# sx1509-breakout_mount_remap5.net
KiCad netlist of a schematic drawn in EAGLE
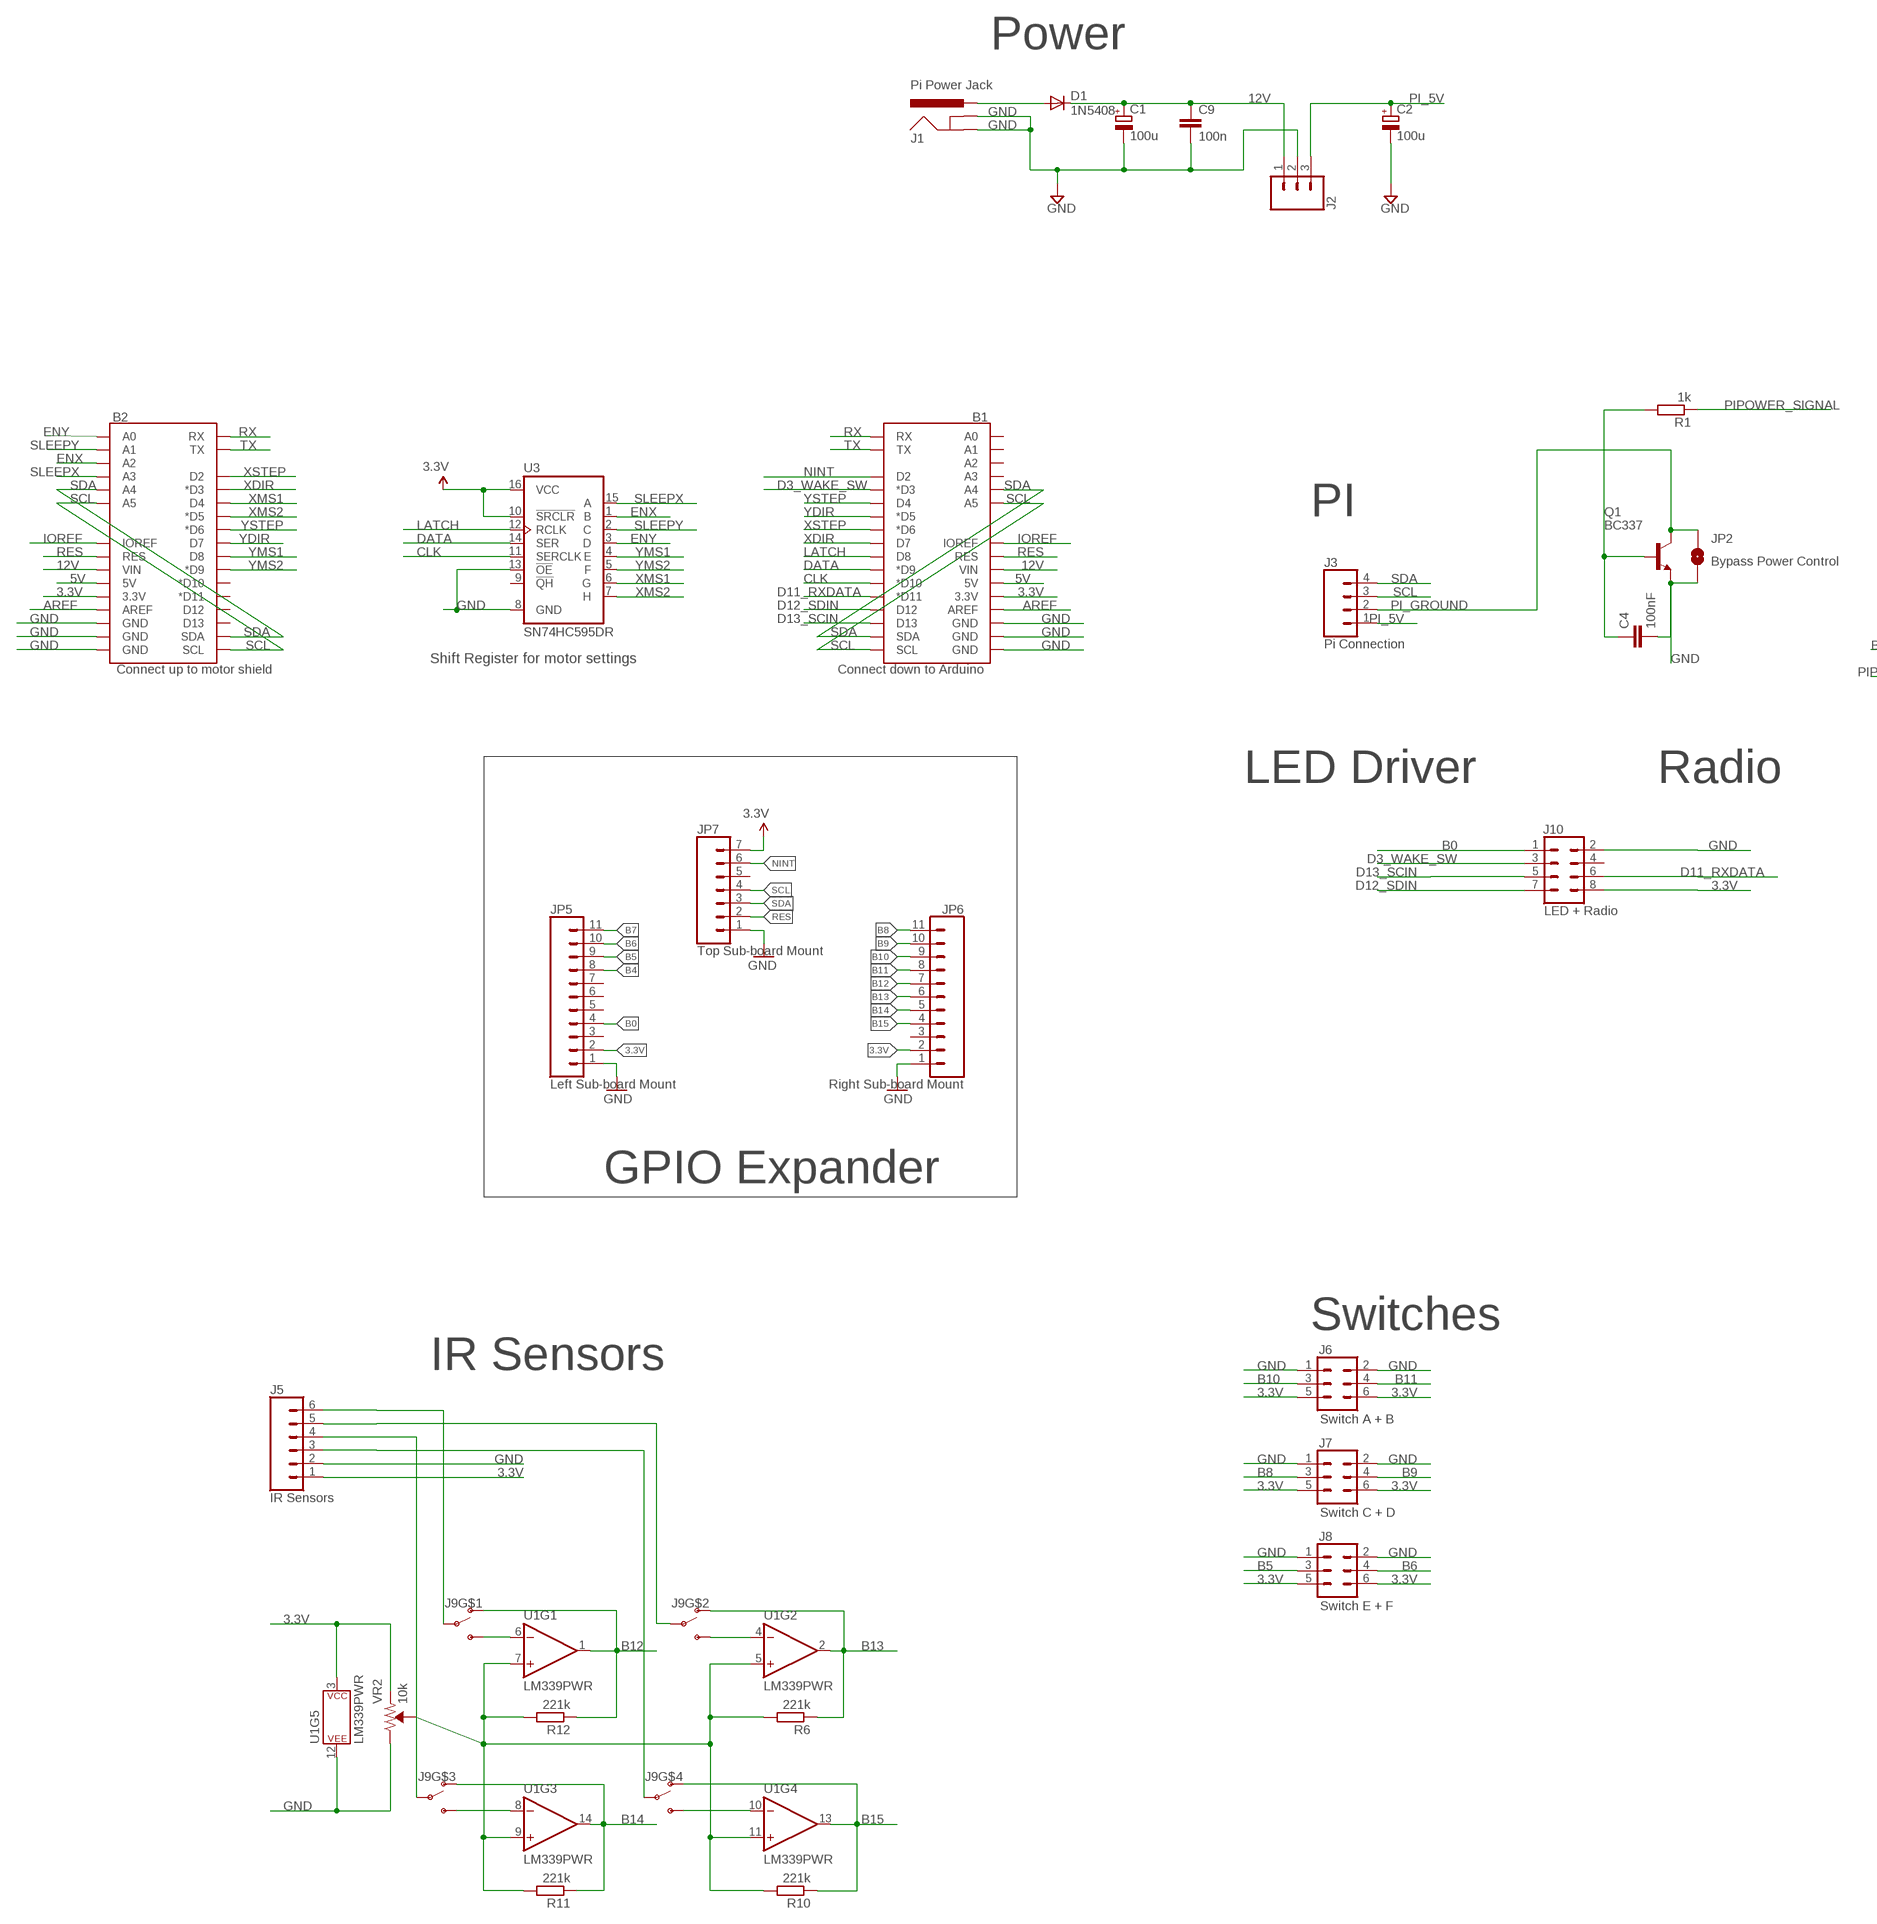
[diagram p0: schematic, sheet 1, part 1 of 2]
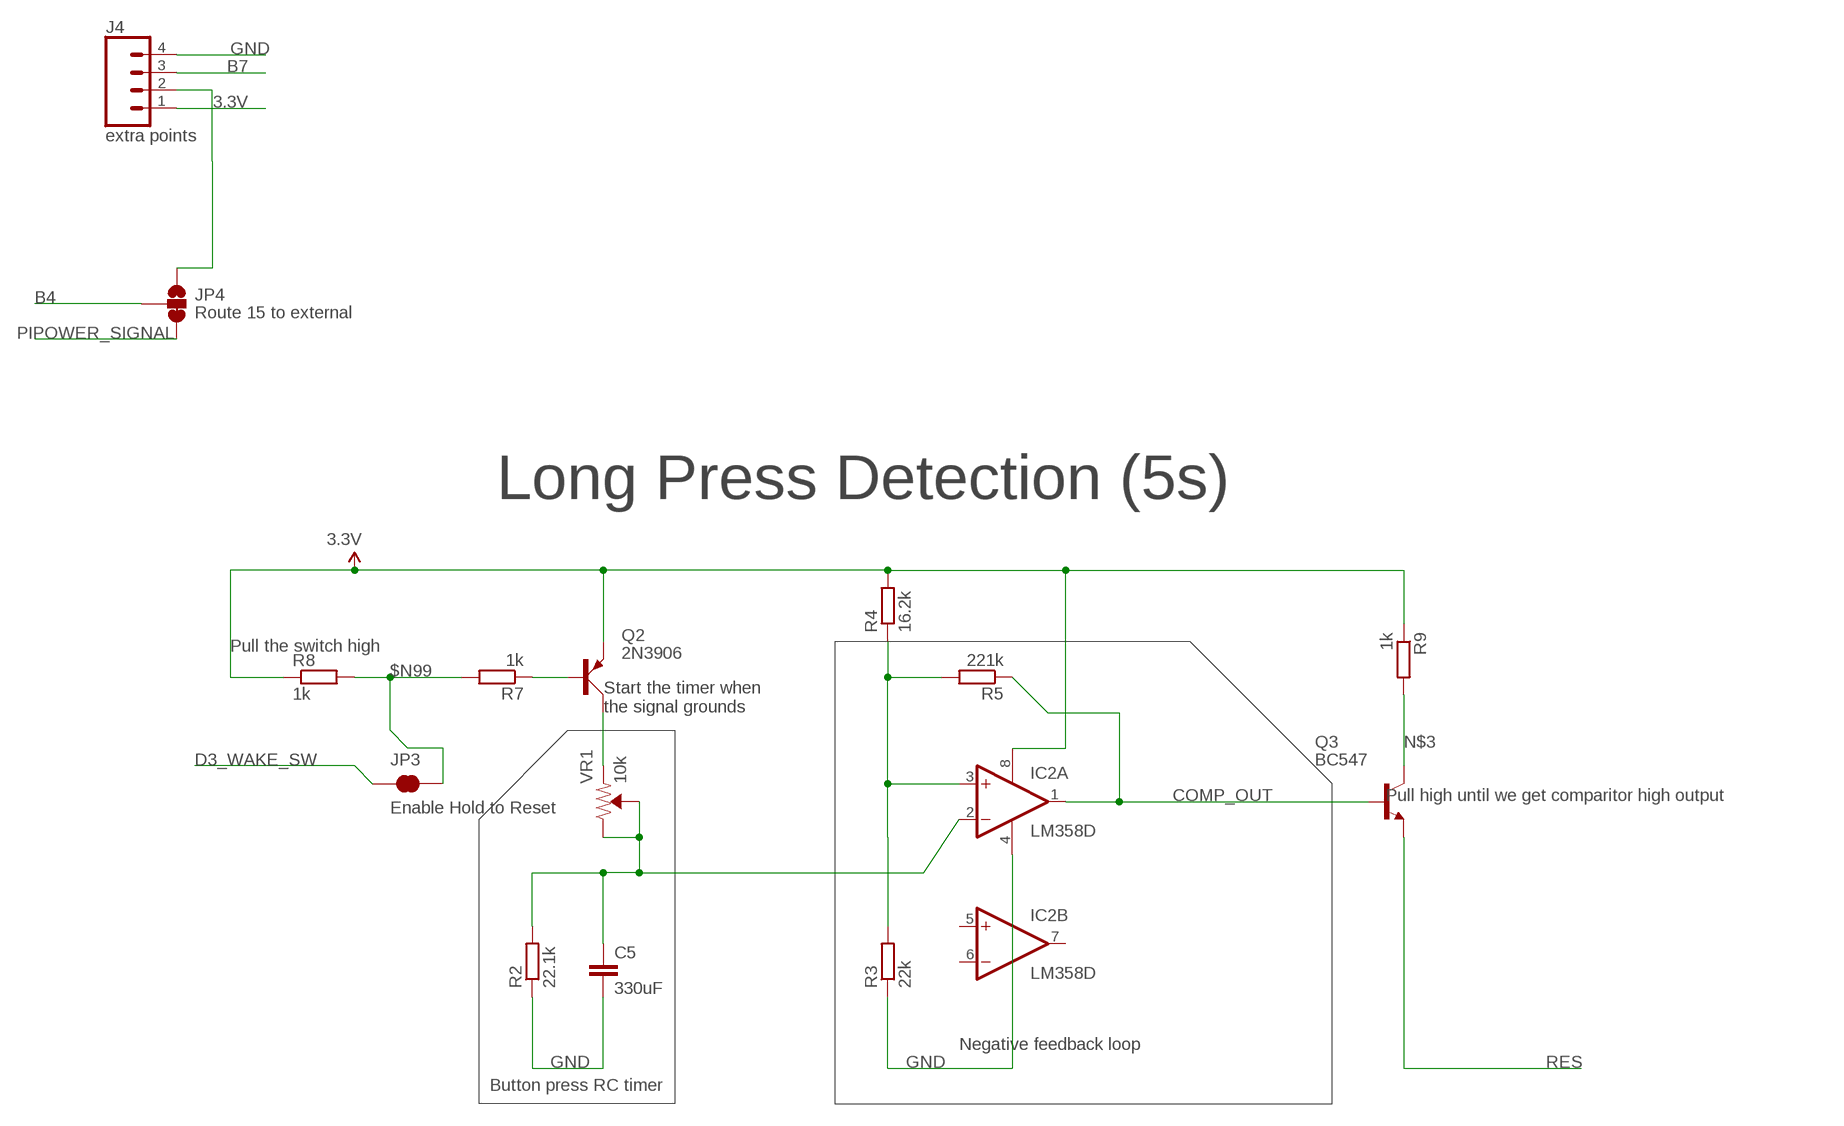
[diagram p1: schematic, sheet 1, part 2 of 2]

(export (version "E")
  (design (tool "Eeschema 10.0.6"))
  (components
    (comp (ref "B1")
      (value "Connect down to Arduino")
      (footprint "eagle-import:UNO_R3_SHIELD_NOLABELS")
      (libsource (lib "eagle-import") (part "ARDUINO_UNO_R3_SHIELDNOLABELS"))
    )
    (comp (ref "B2")
      (value "Connect up to motor shield")
      (footprint "eagle-import:UNO_R3_SHIELD_NOLABELS")
      (libsource (lib "eagle-import") (part "ARDUINO_UNO_R3_SHIELDNOLABELS"))
    )
    (comp (ref "C1")
      (value "100u")
      (footprint "eagle-import:E2-5")
      (libsource (lib "eagle-import") (part "CPOL-EUE2-5"))
    )
    (comp (ref "C2")
      (value "100u")
      (footprint "eagle-import:E2-5")
      (libsource (lib "eagle-import") (part "CPOL-EUE2-5"))
    )
    (comp (ref "C4")
      (value "100nF")
      (footprint "eagle-import:C0805")
      (libsource (lib "eagle-import") (part "resistor_348_C-EUC0805"))
    )
    (comp (ref "C5")
      (value "330uF")
      (footprint "eagle-import:C0805")
      (libsource (lib "eagle-import") (part "resistor_348_C-EUC0805"))
    )
    (comp (ref "C9")
      (value "100n")
      (footprint "eagle-import:C0805")
      (libsource (lib "eagle-import") (part "C-EUC0805"))
    )
    (comp (ref "D1")
      (value "1N5408")
      (footprint "eagle-import:DO15-12")
      (libsource (lib "eagle-import") (part "1N5408"))
    )
    (comp (ref "IC2")
      (value "LM358D")
      (footprint "eagle-import:SO08")
      (libsource (lib "eagle-import") (part "LM358D"))
    )
    (comp (ref "J1")
      (value "Pi Power Jack")
      (footprint "eagle-import:POWER_JACK_PTH_BREAD")
      (libsource (lib "eagle-import") (part "POWER_JACKPTH_BREAD"))
    )
    (comp (ref "J2")
      (value "Header - Right angled, female")
      (footprint "eagle-import:1X03")
      (libsource (lib "eagle-import") (part "CONN_031X03_2.54MM_RA_FEMALE"))
    )
    (comp (ref "J3")
      (value "Pi Connection")
      (footprint "eagle-import:1X04_1.24MM_RA_MALE")
      (libsource (lib "eagle-import") (part "CONN_041X04_1.24MM_RA_MALE"))
    )
    (comp (ref "J4")
      (value "extra points")
      (footprint "eagle-import:1X04_1.24MM_RA_MALE")
      (libsource (lib "eagle-import") (part "CONN_041X04_1.24MM_RA_MALE"))
    )
    (comp (ref "J5")
      (value "IR Sensors")
      (footprint "eagle-import:1X06")
      (libsource (lib "eagle-import") (part "CONN_06SILK_FEMALE_PTH"))
    )
    (comp (ref "J6")
      (value "Switch A + B")
      (footprint "eagle-import:2X3")
      (libsource (lib "eagle-import") (part "CONN_03X22X03_2.54MM_RA_MALE"))
    )
    (comp (ref "J7")
      (value "Switch C + D")
      (footprint "eagle-import:2X3")
      (libsource (lib "eagle-import") (part "CONN_03X22X03_2.54MM_RA_MALE"))
    )
    (comp (ref "J8")
      (value "Switch E + F")
      (footprint "eagle-import:2X3")
      (libsource (lib "eagle-import") (part "CONN_03X22X03_2.54MM_RA_MALE"))
    )
    (comp (ref "J9")
      (value "CONN_04X3")
      (footprint "eagle-import:3X04_1.24MM_RA_MALE")
      (libsource (lib "eagle-import") (part "CONN_04X3"))
    )
    (comp (ref "J10")
      (value "LED + Radio")
      (footprint "eagle-import:2X4")
      (libsource (lib "eagle-import") (part "CONN_04X22X4_1.24MM_RA_MALE"))
    )
    (comp (ref "JP2")
      (value "Bypass Power Control")
      (footprint "eagle-import:SMT-JUMPER_2_NO_SILK_ROUND")
      (libsource (lib "eagle-import") (part "JUMPER-SMT_2_NO_SILK_ROUND"))
    )
    (comp (ref "JP3")
      (value "Enable Hold to Reset")
      (footprint "eagle-import:SMT-JUMPER_2_NC_TRACE_SILK")
      (libsource (lib "eagle-import") (part "JUMPER-SMT_2_NC_TRACE_SILK"))
    )
    (comp (ref "JP4")
      (value "Route 15 to external")
      (footprint "eagle-import:SMT-JUMPER_3_1-NC_TRACE_SILK")
      (libsource (lib "eagle-import") (part "JUMPER-SMT_3_1-NC_TRACE_SILK"))
    )
    (comp (ref "JP5")
      (value "Left Sub-board Mount")
      (footprint "eagle-import:1X11")
      (libsource (lib "eagle-import") (part "CONN_111X11_2.54MM_FEMALE"))
    )
    (comp (ref "JP6")
      (value "Right Sub-board Mount")
      (footprint "eagle-import:1X11")
      (libsource (lib "eagle-import") (part "CONN_111X11_2.54MM_FEMALE"))
    )
    (comp (ref "JP7")
      (value "Top Sub-board Mount")
      (footprint "eagle-import:1X07")
      (libsource (lib "eagle-import") (part "CONN_071X07_2.54MM_FEMALE"))
    )
    (comp (ref "Q1")
      (value "BC337")
      (footprint "eagle-import:TO92")
      (libsource (lib "eagle-import") (part "BC337"))
    )
    (comp (ref "Q2")
      (value "2N3906")
      (footprint "eagle-import:TO92D")
      (libsource (lib "eagle-import") (part "2N3906"))
    )
    (comp (ref "Q3")
      (value "BC547")
      (footprint "eagle-import:TO92")
      (fields (field (name "NOTE") "Pull high until we get comparitor high output"))
      (libsource (lib "eagle-import") (part "BC547"))
    )
    (comp (ref "R1")
      (value "1k")
      (footprint "eagle-import:M0805")
      (libsource (lib "eagle-import") (part "R-EU_M0805"))
    )
    (comp (ref "R2")
      (value "22.1k")
      (footprint "eagle-import:M0805")
      (libsource (lib "eagle-import") (part "R-EU_M0805"))
    )
    (comp (ref "R3")
      (value "22k")
      (footprint "eagle-import:M0805")
      (libsource (lib "eagle-import") (part "R-EU_M0805"))
    )
    (comp (ref "R4")
      (value "16.2k")
      (footprint "eagle-import:M0805")
      (libsource (lib "eagle-import") (part "R-EU_M0805"))
    )
    (comp (ref "R5")
      (value "221k")
      (footprint "eagle-import:M0805")
      (libsource (lib "eagle-import") (part "R-EU_M0805"))
    )
    (comp (ref "R6")
      (value "221k")
      (footprint "eagle-import:M0805")
      (libsource (lib "eagle-import") (part "R-EU_M0805"))
    )
    (comp (ref "R7")
      (value "1k")
      (footprint "eagle-import:M0805")
      (libsource (lib "eagle-import") (part "R-EU_M0805"))
    )
    (comp (ref "R8")
      (value "1k")
      (footprint "eagle-import:M0805")
      (fields (field (name "NOTE") "Pull the switch high"))
      (libsource (lib "eagle-import") (part "R-EU_M0805"))
    )
    (comp (ref "R9")
      (value "1k")
      (footprint "eagle-import:M0805")
      (libsource (lib "eagle-import") (part "R-EU_M0805"))
    )
    (comp (ref "R10")
      (value "221k")
      (footprint "eagle-import:M0805")
      (libsource (lib "eagle-import") (part "R-EU_M0805"))
    )
    (comp (ref "R11")
      (value "221k")
      (footprint "eagle-import:M0805")
      (libsource (lib "eagle-import") (part "R-EU_M0805"))
    )
    (comp (ref "R12")
      (value "221k")
      (footprint "eagle-import:M0805")
      (libsource (lib "eagle-import") (part "R-EU_M0805"))
    )
    (comp (ref "U1")
      (value "LM339PWR")
      (footprint "eagle-import:TSSOP-14")
      (libsource (lib "eagle-import") (part "LM339"))
    )
    (comp (ref "U3")
      (value "SN74HC595DR")
      (footprint "eagle-import:SO16")
      (libsource (lib "eagle-import") (part "SN74HC595DHC"))
    )
    (comp (ref "VR1")
      (value "10k")
      (footprint "eagle-import:TRIMPOT-PTH-3386U")
      (libsource (lib "eagle-import") (part "TRIMPOT-PTH-10MM-KNOB-1/2W-10%"))
    )
    (comp (ref "VR2")
      (value "10k")
      (footprint "eagle-import:TRIMPOT-PTH-3386U")
      (libsource (lib "eagle-import") (part "TRIMPOT-PTH-10MM-KNOB-1/2W-10%"))
    )
  )
  (nets
    (net (code "1") (name "/$N99") (class "Default")
      (node (ref "JP3") (pin "2") (pinfunction "2_2") (pintype "passive"))
      (node (ref "R7") (pin "2") (pinfunction "2_2") (pintype "passive"))
      (node (ref "R8") (pin "2") (pinfunction "2_2") (pintype "passive"))
    )
    (net (code "2") (name "/5V") (class "Default")
      (node (ref "B1") (pin "5V") (pinfunction "5V_5V") (pintype "bidirectional"))
      (node (ref "B2") (pin "5V") (pinfunction "5V_5V") (pintype "bidirectional"))
    )
    (net (code "3") (name "/12V") (class "Default")
      (node (ref "B1") (pin "VIN") (pinfunction "VIN_VIN") (pintype "bidirectional"))
      (node (ref "B2") (pin "VIN") (pinfunction "VIN_VIN") (pintype "bidirectional"))
      (node (ref "C1") (pin "+") (pinfunction "+_+") (pintype "passive"))
      (node (ref "C9") (pin "1") (pinfunction "1_1") (pintype "passive"))
      (node (ref "D1") (pin "C") (pinfunction "C_C") (pintype "passive"))
      (node (ref "J2") (pin "1") (pinfunction "1_1") (pintype "passive"))
    )
    (net (code "4") (name "/AREF") (class "Default")
      (node (ref "B1") (pin "AREF") (pinfunction "AREF_AREF") (pintype "bidirectional"))
      (node (ref "B2") (pin "AREF") (pinfunction "AREF_AREF") (pintype "bidirectional"))
    )
    (net (code "5") (name "/CLK") (class "Default")
      (node (ref "B1") (pin "D10") (pinfunction "*D10_D10") (pintype "bidirectional"))
      (node (ref "U3") (pin "11") (pinfunction "SERCLK_11") (pintype "input"))
    )
    (net (code "6") (name "/COMP_OUT") (class "Default")
      (node (ref "IC2") (pin "1") (pinfunction "OUT_1") (pintype "output"))
      (node (ref "Q3") (pin "2") (pinfunction "B_2") (pintype "passive"))
      (node (ref "R5") (pin "1") (pinfunction "1_1") (pintype "passive"))
    )
    (net (code "7") (name "/D3_WAKE_SW") (class "Default")
      (node (ref "B1") (pin "D3") (pinfunction "*D3_D3") (pintype "bidirectional"))
      (node (ref "J10") (pin "3") (pinfunction "3_3") (pintype "passive"))
      (node (ref "JP3") (pin "1") (pinfunction "1_1") (pintype "passive"))
    )
    (net (code "8") (name "/D11_RXDATA") (class "Default")
      (node (ref "B1") (pin "D11") (pinfunction "*D11_D11") (pintype "bidirectional"))
      (node (ref "J10") (pin "6") (pinfunction "6_6") (pintype "passive"))
    )
    (net (code "9") (name "/D12_SDIN") (class "Default")
      (node (ref "B1") (pin "D12") (pinfunction "D12_D12") (pintype "bidirectional"))
      (node (ref "J10") (pin "7") (pinfunction "7_7") (pintype "passive"))
    )
    (net (code "10") (name "/D13_SCIN") (class "Default")
      (node (ref "B1") (pin "D13") (pinfunction "D13_D13") (pintype "bidirectional"))
      (node (ref "J10") (pin "5") (pinfunction "5_5") (pintype "passive"))
    )
    (net (code "11") (name "/DATA") (class "Default")
      (node (ref "B1") (pin "D9") (pinfunction "*D9_D9") (pintype "bidirectional"))
      (node (ref "U3") (pin "14") (pinfunction "SER_14") (pintype "input"))
    )
    (net (code "12") (name "/ENX") (class "Default")
      (node (ref "B2") (pin "A2") (pinfunction "A2_A2") (pintype "bidirectional"))
      (node (ref "U3") (pin "1") (pinfunction "B_1") (pintype "tri_state"))
    )
    (net (code "13") (name "/ENY") (class "Default")
      (node (ref "B2") (pin "A0") (pinfunction "A0_A0") (pintype "bidirectional"))
      (node (ref "U3") (pin "3") (pinfunction "D_3") (pintype "tri_state"))
    )
    (net (code "14") (name "/IOREF") (class "Default")
      (node (ref "B1") (pin "IOREF") (pinfunction "IOREF_IOREF") (pintype "bidirectional"))
      (node (ref "B2") (pin "IOREF") (pinfunction "IOREF_IOREF") (pintype "bidirectional"))
    )
    (net (code "15") (name "/LATCH") (class "Default")
      (node (ref "B1") (pin "D8") (pinfunction "D8_D8") (pintype "bidirectional"))
      (node (ref "U3") (pin "12") (pinfunction "RCLK_12") (pintype "input"))
    )
    (net (code "16") (name "/N$3") (class "Default")
      (node (ref "Q3") (pin "3") (pinfunction "C_3") (pintype "passive"))
      (node (ref "R9") (pin "2") (pinfunction "2_2") (pintype "passive"))
    )
    (net (code "17") (name "/PIPOWER_SIGNAL") (class "Default")
      (node (ref "JP4") (pin "3") (pinfunction "3_3") (pintype "passive"))
      (node (ref "R1") (pin "1") (pinfunction "1_1") (pintype "passive"))
    )
    (net (code "18") (name "/PI_5V") (class "Default")
      (node (ref "C2") (pin "+") (pinfunction "+_+") (pintype "passive"))
      (node (ref "J2") (pin "3") (pinfunction "3_3") (pintype "passive"))
      (node (ref "J3") (pin "1") (pinfunction "1_1") (pintype "passive"))
    )
    (net (code "19") (name "/PI_GROUND") (class "Default")
      (node (ref "J3") (pin "2") (pinfunction "2_2") (pintype "passive"))
      (node (ref "JP2") (pin "1") (pinfunction "1_1") (pintype "passive"))
      (node (ref "Q1") (pin "3") (pinfunction "C_3") (pintype "passive"))
    )
    (net (code "20") (name "/RX") (class "Default")
      (node (ref "B1") (pin "RX") (pinfunction "RX_RX") (pintype "bidirectional"))
      (node (ref "B2") (pin "RX") (pinfunction "RX_RX") (pintype "bidirectional"))
    )
    (net (code "21") (name "/SLEEPX") (class "Default")
      (node (ref "B2") (pin "A3") (pinfunction "A3_A3") (pintype "bidirectional"))
      (node (ref "U3") (pin "15") (pinfunction "A_15") (pintype "tri_state"))
    )
    (net (code "22") (name "/SLEEPY") (class "Default")
      (node (ref "B2") (pin "A1") (pinfunction "A1_A1") (pintype "bidirectional"))
      (node (ref "U3") (pin "2") (pinfunction "C_2") (pintype "tri_state"))
    )
    (net (code "23") (name "/TX") (class "Default")
      (node (ref "B1") (pin "TX") (pinfunction "TX_TX") (pintype "bidirectional"))
      (node (ref "B2") (pin "TX") (pinfunction "TX_TX") (pintype "bidirectional"))
    )
    (net (code "24") (name "/XDIR") (class "Default")
      (node (ref "B1") (pin "D7") (pinfunction "D7_D7") (pintype "bidirectional"))
      (node (ref "B2") (pin "D3") (pinfunction "*D3_D3") (pintype "bidirectional"))
    )
    (net (code "25") (name "/XMS1") (class "Default")
      (node (ref "B2") (pin "D4") (pinfunction "D4_D4") (pintype "bidirectional"))
      (node (ref "U3") (pin "6") (pinfunction "G_6") (pintype "tri_state"))
    )
    (net (code "26") (name "/XMS2") (class "Default")
      (node (ref "B2") (pin "D5") (pinfunction "*D5_D5") (pintype "bidirectional"))
      (node (ref "U3") (pin "7") (pinfunction "H_7") (pintype "tri_state"))
    )
    (net (code "27") (name "/XSTEP") (class "Default")
      (node (ref "B1") (pin "D6") (pinfunction "*D6_D6") (pintype "bidirectional"))
      (node (ref "B2") (pin "D2") (pinfunction "D2_D2") (pintype "bidirectional"))
    )
    (net (code "28") (name "/YDIR") (class "Default")
      (node (ref "B1") (pin "D5") (pinfunction "*D5_D5") (pintype "bidirectional"))
      (node (ref "B2") (pin "D7") (pinfunction "D7_D7") (pintype "bidirectional"))
    )
    (net (code "29") (name "/YMS1") (class "Default")
      (node (ref "B2") (pin "D8") (pinfunction "D8_D8") (pintype "bidirectional"))
      (node (ref "U3") (pin "4") (pinfunction "E_4") (pintype "tri_state"))
    )
    (net (code "30") (name "/YMS2") (class "Default")
      (node (ref "B2") (pin "D9") (pinfunction "*D9_D9") (pintype "bidirectional"))
      (node (ref "U3") (pin "5") (pinfunction "F_5") (pintype "tri_state"))
    )
    (net (code "31") (name "/YSTEP") (class "Default")
      (node (ref "B1") (pin "D4") (pinfunction "D4_D4") (pintype "bidirectional"))
      (node (ref "B2") (pin "D6") (pinfunction "*D6_D6") (pintype "bidirectional"))
    )
    (net (code "32") (name "3.3V") (class "Default")
      (node (ref "B1") (pin "3.3V") (pinfunction "3.3V_3.3V") (pintype "bidirectional"))
      (node (ref "B2") (pin "3.3V") (pinfunction "3.3V_3.3V") (pintype "bidirectional"))
      (node (ref "IC2") (pin "8") (pinfunction "V+_8") (pintype "power_in"))
      (node (ref "J10") (pin "8") (pinfunction "8_8") (pintype "passive"))
      (node (ref "J4") (pin "1") (pinfunction "1_1") (pintype "passive"))
      (node (ref "J5") (pin "1") (pinfunction "1_1") (pintype "passive"))
      (node (ref "J6") (pin "5") (pinfunction "5_5") (pintype "bidirectional"))
      (node (ref "J6") (pin "6") (pinfunction "6_6") (pintype "bidirectional"))
      (node (ref "J7") (pin "5") (pinfunction "5_5") (pintype "bidirectional"))
      (node (ref "J7") (pin "6") (pinfunction "6_6") (pintype "bidirectional"))
      (node (ref "J8") (pin "5") (pinfunction "5_5") (pintype "bidirectional"))
      (node (ref "J8") (pin "6") (pinfunction "6_6") (pintype "bidirectional"))
      (node (ref "JP5") (pin "2") (pinfunction "2_2") (pintype "passive"))
      (node (ref "JP6") (pin "2") (pinfunction "2_2") (pintype "passive"))
      (node (ref "JP7") (pin "7") (pinfunction "7_7") (pintype "passive"))
      (node (ref "Q2") (pin "E") (pinfunction "E_E") (pintype "passive"))
      (node (ref "R4") (pin "2") (pinfunction "2_2") (pintype "passive"))
      (node (ref "R8") (pin "1") (pinfunction "1_1") (pintype "passive"))
      (node (ref "R9") (pin "1") (pinfunction "1_1") (pintype "passive"))
      (node (ref "U1") (pin "3") (pinfunction "P$V+_3") (pintype "bidirectional"))
      (node (ref "U3") (pin "10") (pinfunction "~{SRCLR}_10") (pintype "input"))
      (node (ref "U3") (pin "16") (pinfunction "VCC_16") (pintype "power_in"))
      (node (ref "VR2") (pin "1") (pinfunction "CCW_1") (pintype "passive"))
    )
    (net (code "33") (name "B0") (class "Default")
      (node (ref "J10") (pin "1") (pinfunction "1_1") (pintype "passive"))
      (node (ref "JP5") (pin "4") (pinfunction "4_4") (pintype "passive"))
    )
    (net (code "34") (name "B4") (class "Default")
      (node (ref "JP4") (pin "2") (pinfunction "2_2") (pintype "passive"))
      (node (ref "JP5") (pin "8") (pinfunction "8_8") (pintype "passive"))
    )
    (net (code "35") (name "B5") (class "Default")
      (node (ref "J8") (pin "3") (pinfunction "3_3") (pintype "bidirectional"))
      (node (ref "JP5") (pin "9") (pinfunction "9_9") (pintype "passive"))
    )
    (net (code "36") (name "B6") (class "Default")
      (node (ref "J8") (pin "4") (pinfunction "4_4") (pintype "bidirectional"))
      (node (ref "JP5") (pin "10") (pinfunction "10_10") (pintype "passive"))
    )
    (net (code "37") (name "B7") (class "Default")
      (node (ref "J4") (pin "3") (pinfunction "3_3") (pintype "passive"))
      (node (ref "JP5") (pin "11") (pinfunction "11_11") (pintype "passive"))
    )
    (net (code "38") (name "B8") (class "Default")
      (node (ref "J7") (pin "3") (pinfunction "3_3") (pintype "bidirectional"))
      (node (ref "JP6") (pin "11") (pinfunction "11_11") (pintype "passive"))
    )
    (net (code "39") (name "B9") (class "Default")
      (node (ref "J7") (pin "4") (pinfunction "4_4") (pintype "bidirectional"))
      (node (ref "JP6") (pin "10") (pinfunction "10_10") (pintype "passive"))
    )
    (net (code "40") (name "B10") (class "Default")
      (node (ref "J6") (pin "3") (pinfunction "3_3") (pintype "bidirectional"))
      (node (ref "JP6") (pin "9") (pinfunction "9_9") (pintype "passive"))
    )
    (net (code "41") (name "B11") (class "Default")
      (node (ref "J6") (pin "4") (pinfunction "4_4") (pintype "bidirectional"))
      (node (ref "JP6") (pin "8") (pinfunction "8_8") (pintype "passive"))
    )
    (net (code "42") (name "B12") (class "Default")
      (node (ref "J9") (pin "2") (pinfunction "O_2") (pintype "passive"))
      (node (ref "JP6") (pin "7") (pinfunction "7_7") (pintype "passive"))
      (node (ref "R12") (pin "1") (pinfunction "1_1") (pintype "passive"))
      (node (ref "U1") (pin "1") (pinfunction "OUT_1") (pintype "output"))
    )
    (net (code "43") (name "B13") (class "Default")
      (node (ref "J9") (pin "5") (pinfunction "O_5") (pintype "passive"))
      (node (ref "JP6") (pin "6") (pinfunction "6_6") (pintype "passive"))
      (node (ref "R6") (pin "1") (pinfunction "1_1") (pintype "passive"))
      (node (ref "U1") (pin "2") (pinfunction "OUT_2") (pintype "output"))
    )
    (net (code "44") (name "B14") (class "Default")
      (node (ref "J9") (pin "8") (pinfunction "O_8") (pintype "passive"))
      (node (ref "JP6") (pin "5") (pinfunction "5_5") (pintype "passive"))
      (node (ref "R11") (pin "1") (pinfunction "1_1") (pintype "passive"))
      (node (ref "U1") (pin "14") (pinfunction "OUT_14") (pintype "output"))
    )
    (net (code "45") (name "B15") (class "Default")
      (node (ref "J9") (pin "11") (pinfunction "O_11") (pintype "passive"))
      (node (ref "JP6") (pin "4") (pinfunction "4_4") (pintype "passive"))
      (node (ref "R10") (pin "1") (pinfunction "1_1") (pintype "passive"))
      (node (ref "U1") (pin "13") (pinfunction "OUT_13") (pintype "output"))
    )
    (net (code "46") (name "GND") (class "Default")
      (node (ref "B1") (pin "GND@0") (pinfunction "GND_GND@0") (pintype "bidirectional"))
      (node (ref "B1") (pin "GND@1") (pinfunction "GND_GND@1") (pintype "bidirectional"))
      (node (ref "B1") (pin "GND@2") (pinfunction "GND_GND@2") (pintype "bidirectional"))
      (node (ref "B2") (pin "GND@0") (pinfunction "GND_GND@0") (pintype "bidirectional"))
      (node (ref "B2") (pin "GND@1") (pinfunction "GND_GND@1") (pintype "bidirectional"))
      (node (ref "B2") (pin "GND@2") (pinfunction "GND_GND@2") (pintype "bidirectional"))
      (node (ref "C1") (pin "-") (pinfunction "-_-") (pintype "passive"))
      (node (ref "C2") (pin "-") (pinfunction "-_-") (pintype "passive"))
      (node (ref "C4") (pin "2") (pinfunction "2_2") (pintype "passive"))
      (node (ref "C5") (pin "2") (pinfunction "2_2") (pintype "passive"))
      (node (ref "C9") (pin "2") (pinfunction "2_2") (pintype "passive"))
      (node (ref "IC2") (pin "4") (pinfunction "V-_4") (pintype "power_in"))
      (node (ref "J1") (pin "GND") (pinfunction "GND_GND") (pintype "bidirectional"))
      (node (ref "J1") (pin "GNDBREAK") (pinfunction "GNDBREAK_GNDBREAK") (pintype "bidirectional"))
      (node (ref "J10") (pin "2") (pinfunction "2_2") (pintype "passive"))
      (node (ref "J2") (pin "2") (pinfunction "2_2") (pintype "passive"))
      (node (ref "J4") (pin "4") (pinfunction "4_4") (pintype "passive"))
      (node (ref "J5") (pin "2") (pinfunction "2_2") (pintype "passive"))
      (node (ref "J6") (pin "1") (pinfunction "1_1") (pintype "bidirectional"))
      (node (ref "J6") (pin "2") (pinfunction "2_2") (pintype "bidirectional"))
      (node (ref "J7") (pin "1") (pinfunction "1_1") (pintype "bidirectional"))
      (node (ref "J7") (pin "2") (pinfunction "2_2") (pintype "bidirectional"))
      (node (ref "J8") (pin "1") (pinfunction "1_1") (pintype "bidirectional"))
      (node (ref "J8") (pin "2") (pinfunction "2_2") (pintype "bidirectional"))
      (node (ref "JP2") (pin "2") (pinfunction "2_2") (pintype "passive"))
      (node (ref "JP5") (pin "1") (pinfunction "1_1") (pintype "passive"))
      (node (ref "JP6") (pin "1") (pinfunction "1_1") (pintype "passive"))
      (node (ref "JP7") (pin "1") (pinfunction "1_1") (pintype "passive"))
      (node (ref "Q1") (pin "1") (pinfunction "E_1") (pintype "passive"))
      (node (ref "R2") (pin "1") (pinfunction "1_1") (pintype "passive"))
      (node (ref "R3") (pin "1") (pinfunction "1_1") (pintype "passive"))
      (node (ref "U1") (pin "12") (pinfunction "P$V-_12") (pintype "bidirectional"))
      (node (ref "U3") (pin "13") (pinfunction "~{OE}_13") (pintype "input"))
      (node (ref "U3") (pin "8") (pinfunction "GND_8") (pintype "power_in"))
      (node (ref "VR2") (pin "3") (pinfunction "CW_3") (pintype "passive"))
    )
    (net (code "47") (name "NINT") (class "Default")
      (node (ref "B1") (pin "D2") (pinfunction "D2_D2") (pintype "bidirectional"))
      (node (ref "JP7") (pin "6") (pinfunction "6_6") (pintype "passive"))
    )
    (net (code "48") (name "Net-(D1-PadA)") (class "Default")
      (node (ref "D1") (pin "A") (pinfunction "A_A") (pintype "passive"))
      (node (ref "J1") (pin "PWR") (pinfunction "PWR_PWR") (pintype "bidirectional"))
    )
    (net (code "49") (name "Net-(IC2A-+IN)") (class "Default")
      (node (ref "IC2") (pin "3") (pinfunction "+IN_3") (pintype "input"))
      (node (ref "R3") (pin "2") (pinfunction "2_2") (pintype "passive"))
      (node (ref "R4") (pin "1") (pinfunction "1_1") (pintype "passive"))
      (node (ref "R5") (pin "2") (pinfunction "2_2") (pintype "passive"))
    )
    (net (code "50") (name "Net-(IC2A--IN)") (class "Default")
      (node (ref "C5") (pin "1") (pinfunction "1_1") (pintype "passive"))
      (node (ref "IC2") (pin "2") (pinfunction "-IN_2") (pintype "input"))
      (node (ref "R2") (pin "2") (pinfunction "2_2") (pintype "passive"))
      (node (ref "VR1") (pin "2") (pinfunction "WIPER_2") (pintype "passive"))
      (node (ref "VR1") (pin "3") (pinfunction "CW_3") (pintype "passive"))
    )
    (net (code "51") (name "Net-(J4-Pad2)") (class "Default")
      (node (ref "J4") (pin "2") (pinfunction "2_2") (pintype "passive"))
      (node (ref "JP4") (pin "1") (pinfunction "1_1") (pintype "passive"))
    )
    (net (code "52") (name "Net-(J9A-P)") (class "Default")
      (node (ref "J5") (pin "6") (pinfunction "6_6") (pintype "passive"))
      (node (ref "J9") (pin "1") (pinfunction "P_1") (pintype "passive"))
    )
    (net (code "53") (name "Net-(J9A-S)") (class "Default")
      (node (ref "J9") (pin "3") (pinfunction "S_3") (pintype "passive"))
      (node (ref "U1") (pin "6") (pinfunction "-IN_6") (pintype "input"))
    )
    (net (code "54") (name "Net-(J9B-P)") (class "Default")
      (node (ref "J5") (pin "5") (pinfunction "5_5") (pintype "passive"))
      (node (ref "J9") (pin "4") (pinfunction "P_4") (pintype "passive"))
    )
    (net (code "55") (name "Net-(J9B-S)") (class "Default")
      (node (ref "J9") (pin "6") (pinfunction "S_6") (pintype "passive"))
      (node (ref "U1") (pin "4") (pinfunction "-IN_4") (pintype "input"))
    )
    (net (code "56") (name "Net-(J9C-P)") (class "Default")
      (node (ref "J5") (pin "4") (pinfunction "4_4") (pintype "passive"))
      (node (ref "J9") (pin "7") (pinfunction "P_7") (pintype "passive"))
    )
    (net (code "57") (name "Net-(J9C-S)") (class "Default")
      (node (ref "J9") (pin "9") (pinfunction "S_9") (pintype "passive"))
      (node (ref "U1") (pin "8") (pinfunction "-IN_8") (pintype "input"))
    )
    (net (code "58") (name "Net-(J9D-P)") (class "Default")
      (node (ref "J5") (pin "3") (pinfunction "3_3") (pintype "passive"))
      (node (ref "J9") (pin "10") (pinfunction "P_10") (pintype "passive"))
    )
    (net (code "59") (name "Net-(J9D-S)") (class "Default")
      (node (ref "J9") (pin "12") (pinfunction "S_12") (pintype "passive"))
      (node (ref "U1") (pin "10") (pinfunction "-IN_10") (pintype "input"))
    )
    (net (code "60") (name "Net-(Q1-B)") (class "Default")
      (node (ref "C4") (pin "1") (pinfunction "1_1") (pintype "passive"))
      (node (ref "Q1") (pin "2") (pinfunction "B_2") (pintype "passive"))
      (node (ref "R1") (pin "2") (pinfunction "2_2") (pintype "passive"))
    )
    (net (code "61") (name "Net-(Q2-PadB)") (class "Default")
      (node (ref "Q2") (pin "B") (pinfunction "B_B") (pintype "passive"))
      (node (ref "R7") (pin "1") (pinfunction "1_1") (pintype "passive"))
    )
    (net (code "62") (name "Net-(U1A-+IN)") (class "Default")
      (node (ref "R10") (pin "2") (pinfunction "2_2") (pintype "passive"))
      (node (ref "R11") (pin "2") (pinfunction "2_2") (pintype "passive"))
      (node (ref "R12") (pin "2") (pinfunction "2_2") (pintype "passive"))
      (node (ref "R6") (pin "2") (pinfunction "2_2") (pintype "passive"))
      (node (ref "U1") (pin "11") (pinfunction "+IN_11") (pintype "input"))
      (node (ref "U1") (pin "5") (pinfunction "+IN_5") (pintype "input"))
      (node (ref "U1") (pin "7") (pinfunction "+IN_7") (pintype "input"))
      (node (ref "U1") (pin "9") (pinfunction "+IN_9") (pintype "input"))
      (node (ref "VR2") (pin "2") (pinfunction "WIPER_2") (pintype "passive"))
    )
    (net (code "63") (name "Net-(VR1-CCW)") (class "Default")
      (node (ref "Q2") (pin "C") (pinfunction "C_C") (pintype "passive"))
      (node (ref "VR1") (pin "1") (pinfunction "CCW_1") (pintype "passive"))
    )
    (net (code "64") (name "RES") (class "Default")
      (node (ref "B1") (pin "RES") (pinfunction "RES_RES") (pintype "bidirectional"))
      (node (ref "B2") (pin "RES") (pinfunction "RES_RES") (pintype "bidirectional"))
      (node (ref "JP7") (pin "2") (pinfunction "2_2") (pintype "passive"))
      (node (ref "Q3") (pin "1") (pinfunction "E_1") (pintype "passive"))
    )
    (net (code "65") (name "SCL") (class "Default")
      (node (ref "B1") (pin "A5") (pinfunction "A5_A5") (pintype "bidirectional"))
      (node (ref "B1") (pin "SCL") (pinfunction "SCL_SCL") (pintype "bidirectional"))
      (node (ref "B2") (pin "A5") (pinfunction "A5_A5") (pintype "bidirectional"))
      (node (ref "B2") (pin "SCL") (pinfunction "SCL_SCL") (pintype "bidirectional"))
      (node (ref "J3") (pin "3") (pinfunction "3_3") (pintype "passive"))
      (node (ref "JP7") (pin "4") (pinfunction "4_4") (pintype "passive"))
    )
    (net (code "66") (name "SDA") (class "Default")
      (node (ref "B1") (pin "A4") (pinfunction "A4_A4") (pintype "bidirectional"))
      (node (ref "B1") (pin "SDA") (pinfunction "SDA_SDA") (pintype "bidirectional"))
      (node (ref "B2") (pin "A4") (pinfunction "A4_A4") (pintype "bidirectional"))
      (node (ref "B2") (pin "SDA") (pinfunction "SDA_SDA") (pintype "bidirectional"))
      (node (ref "J3") (pin "4") (pinfunction "4_4") (pintype "passive"))
      (node (ref "JP7") (pin "3") (pinfunction "3_3") (pintype "passive"))
    )
    (net (code "67") (name "unconnected-(B1-PadA0)") (class "Default")
      (node (ref "B1") (pin "A0") (pinfunction "A0_A0") (pintype "bidirectional"))
    )
    (net (code "68") (name "unconnected-(B1-PadA1)") (class "Default")
      (node (ref "B1") (pin "A1") (pinfunction "A1_A1") (pintype "bidirectional"))
    )
    (net (code "69") (name "unconnected-(B1-PadA2)") (class "Default")
      (node (ref "B1") (pin "A2") (pinfunction "A2_A2") (pintype "bidirectional"))
    )
    (net (code "70") (name "unconnected-(B1-PadA3)") (class "Default")
      (node (ref "B1") (pin "A3") (pinfunction "A3_A3") (pintype "bidirectional"))
    )
    (net (code "71") (name "unconnected-(B2-*D10-PadD10)") (class "Default")
      (node (ref "B2") (pin "D10") (pinfunction "*D10_D10") (pintype "bidirectional"))
    )
    (net (code "72") (name "unconnected-(B2-*D11-PadD11)") (class "Default")
      (node (ref "B2") (pin "D11") (pinfunction "*D11_D11") (pintype "bidirectional"))
    )
    (net (code "73") (name "unconnected-(B2-PadD12)") (class "Default")
      (node (ref "B2") (pin "D12") (pinfunction "D12_D12") (pintype "bidirectional"))
    )
    (net (code "74") (name "unconnected-(B2-PadD13)") (class "Default")
      (node (ref "B2") (pin "D13") (pinfunction "D13_D13") (pintype "bidirectional"))
    )
    (net (code "75") (name "unconnected-(IC2B-+IN-Pad5)") (class "Default")
      (node (ref "IC2") (pin "5") (pinfunction "+IN_5") (pintype "input"))
    )
    (net (code "76") (name "unconnected-(IC2B--IN-Pad6)") (class "Default")
      (node (ref "IC2") (pin "6") (pinfunction "-IN_6") (pintype "input"))
    )
    (net (code "77") (name "unconnected-(IC2B-OUT-Pad7)") (class "Default")
      (node (ref "IC2") (pin "7") (pinfunction "OUT_7") (pintype "output"))
    )
    (net (code "78") (name "unconnected-(J10-Pad4)") (class "Default")
      (node (ref "J10") (pin "4") (pinfunction "4_4") (pintype "passive"))
    )
    (net (code "79") (name "unconnected-(JP5-Pad3)") (class "Default")
      (node (ref "JP5") (pin "3") (pinfunction "3_3") (pintype "passive"))
    )
    (net (code "80") (name "unconnected-(JP5-Pad5)") (class "Default")
      (node (ref "JP5") (pin "5") (pinfunction "5_5") (pintype "passive"))
    )
    (net (code "81") (name "unconnected-(JP5-Pad6)") (class "Default")
      (node (ref "JP5") (pin "6") (pinfunction "6_6") (pintype "passive"))
    )
    (net (code "82") (name "unconnected-(JP5-Pad7)") (class "Default")
      (node (ref "JP5") (pin "7") (pinfunction "7_7") (pintype "passive"))
    )
    (net (code "83") (name "unconnected-(JP6-Pad3)") (class "Default")
      (node (ref "JP6") (pin "3") (pinfunction "3_3") (pintype "passive"))
    )
    (net (code "84") (name "unconnected-(JP7-Pad5)") (class "Default")
      (node (ref "JP7") (pin "5") (pinfunction "5_5") (pintype "passive"))
    )
    (net (code "85") (name "unconnected-(U3-~{QH}-Pad9)") (class "Default")
      (node (ref "U3") (pin "9") (pinfunction "~{QH}_9") (pintype "output"))
    )
  )
)
